# arduino2.net
KiCad netlist of a schematic drawn in EAGLE
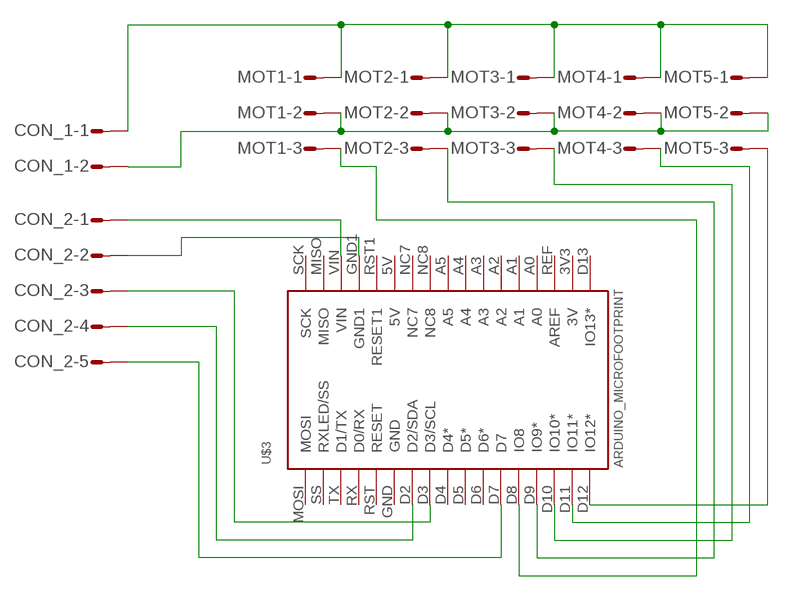
[diagram p0: schematic, sheet 1]

(export (version "E")
  (design (tool "Eeschema 10.0.6"))
  (components
    (comp (ref "CON_1")
      (value "S02P")
      (footprint "eagle-import:S02P")
      (libsource (lib "eagle-import") (part "S02P"))
    )
    (comp (ref "CON_2")
      (value "S05P")
      (footprint "eagle-import:S05P")
      (libsource (lib "eagle-import") (part "S05P"))
    )
    (comp (ref "MOT1")
      (value "S03P")
      (footprint "eagle-import:S03P")
      (libsource (lib "eagle-import") (part "S03P"))
    )
    (comp (ref "MOT2")
      (value "S03P")
      (footprint "eagle-import:S03P")
      (libsource (lib "eagle-import") (part "S03P"))
    )
    (comp (ref "MOT3")
      (value "S03P")
      (footprint "eagle-import:S03P")
      (libsource (lib "eagle-import") (part "S03P"))
    )
    (comp (ref "MOT4")
      (value "S03P")
      (footprint "eagle-import:S03P")
      (libsource (lib "eagle-import") (part "S03P"))
    )
    (comp (ref "MOT5")
      (value "S03P")
      (footprint "eagle-import:S03P")
      (libsource (lib "eagle-import") (part "S03P"))
    )
    (comp (ref "U$3")
      (value "ARDUINO_MICROFOOTPRINT")
      (footprint "eagle-import:ARDUINO-MICRO")
      (libsource (lib "eagle-import") (part "ARDUINO_MICROFOOTPRINT"))
    )
  )
  (nets
    (net (code "1") (name "Net-(CON_1A-S)") (class "Default")
      (node (ref "CON_1") (pin "1") (pinfunction "S_1") (pintype "passive"))
      (node (ref "MOT1") (pin "1") (pinfunction "S_1") (pintype "passive"))
      (node (ref "MOT2") (pin "1") (pinfunction "S_1") (pintype "passive"))
      (node (ref "MOT3") (pin "1") (pinfunction "S_1") (pintype "passive"))
      (node (ref "MOT4") (pin "1") (pinfunction "S_1") (pintype "passive"))
      (node (ref "MOT5") (pin "1") (pinfunction "S_1") (pintype "passive"))
    )
    (net (code "2") (name "Net-(CON_1B-S)") (class "Default")
      (node (ref "CON_1") (pin "2") (pinfunction "S_2") (pintype "passive"))
      (node (ref "MOT1") (pin "2") (pinfunction "S_2") (pintype "passive"))
      (node (ref "MOT2") (pin "2") (pinfunction "S_2") (pintype "passive"))
      (node (ref "MOT3") (pin "2") (pinfunction "S_2") (pintype "passive"))
      (node (ref "MOT4") (pin "2") (pinfunction "S_2") (pintype "passive"))
      (node (ref "MOT5") (pin "2") (pinfunction "S_2") (pintype "passive"))
    )
    (net (code "3") (name "Net-(CON_2A-S)") (class "Default")
      (node (ref "CON_2") (pin "1") (pinfunction "S_1") (pintype "passive"))
      (node (ref "U$3") (pin "VIN") (pinfunction "VIN_VIN") (pintype "bidirectional"))
    )
    (net (code "4") (name "Net-(CON_2B-S)") (class "Default")
      (node (ref "CON_2") (pin "2") (pinfunction "S_2") (pintype "passive"))
      (node (ref "U$3") (pin "GND1") (pinfunction "GND1_GND1") (pintype "bidirectional"))
    )
    (net (code "5") (name "Net-(CON_2C-S)") (class "Default")
      (node (ref "CON_2") (pin "3") (pinfunction "S_3") (pintype "passive"))
      (node (ref "U$3") (pin "D3") (pinfunction "D3/SCL_D3") (pintype "bidirectional"))
    )
    (net (code "6") (name "Net-(CON_2D-S)") (class "Default")
      (node (ref "CON_2") (pin "4") (pinfunction "S_4") (pintype "passive"))
      (node (ref "U$3") (pin "D2") (pinfunction "D2/SDA_D2") (pintype "bidirectional"))
    )
    (net (code "7") (name "Net-(CON_2E-S)") (class "Default")
      (node (ref "CON_2") (pin "5") (pinfunction "S_5") (pintype "passive"))
      (node (ref "U$3") (pin "D7") (pinfunction "D7_D7") (pintype "bidirectional"))
    )
    (net (code "8") (name "Net-(MOT1C-S)") (class "Default")
      (node (ref "MOT1") (pin "3") (pinfunction "S_3") (pintype "passive"))
      (node (ref "U$3") (pin "D8") (pinfunction "IO8_D8") (pintype "bidirectional"))
    )
    (net (code "9") (name "Net-(MOT2C-S)") (class "Default")
      (node (ref "MOT2") (pin "3") (pinfunction "S_3") (pintype "passive"))
      (node (ref "U$3") (pin "D9") (pinfunction "IO9*_D9") (pintype "bidirectional"))
    )
    (net (code "10") (name "Net-(MOT3C-S)") (class "Default")
      (node (ref "MOT3") (pin "3") (pinfunction "S_3") (pintype "passive"))
      (node (ref "U$3") (pin "D10") (pinfunction "IO10*_D10") (pintype "bidirectional"))
    )
    (net (code "11") (name "Net-(MOT4C-S)") (class "Default")
      (node (ref "MOT4") (pin "3") (pinfunction "S_3") (pintype "passive"))
      (node (ref "U$3") (pin "D11") (pinfunction "IO11*_D11") (pintype "bidirectional"))
    )
    (net (code "12") (name "Net-(MOT5C-S)") (class "Default")
      (node (ref "MOT5") (pin "3") (pinfunction "S_3") (pintype "passive"))
      (node (ref "U$3") (pin "D12") (pinfunction "IO12*_D12") (pintype "bidirectional"))
    )
    (net (code "13") (name "unconnected-(U$3-3V-Pad3V3)") (class "Default")
      (node (ref "U$3") (pin "3V3") (pinfunction "3V_3V3") (pintype "bidirectional"))
    )
    (net (code "14") (name "unconnected-(U$3-AREF-PadREF)") (class "Default")
      (node (ref "U$3") (pin "REF") (pinfunction "AREF_REF") (pintype "bidirectional"))
    )
    (net (code "15") (name "unconnected-(U$3-D0{slash}RX-PadRX)") (class "Default")
      (node (ref "U$3") (pin "RX") (pinfunction "D0/RX_RX") (pintype "bidirectional"))
    )
    (net (code "16") (name "unconnected-(U$3-D1{slash}TX-PadTX)") (class "Default")
      (node (ref "U$3") (pin "TX") (pinfunction "D1/TX_TX") (pintype "bidirectional"))
    )
    (net (code "17") (name "unconnected-(U$3-D4*-PadD4)") (class "Default")
      (node (ref "U$3") (pin "D4") (pinfunction "D4*_D4") (pintype "bidirectional"))
    )
    (net (code "18") (name "unconnected-(U$3-D5*-PadD5)") (class "Default")
      (node (ref "U$3") (pin "D5") (pinfunction "D5*_D5") (pintype "bidirectional"))
    )
    (net (code "19") (name "unconnected-(U$3-D6*-PadD6)") (class "Default")
      (node (ref "U$3") (pin "D6") (pinfunction "D6*_D6") (pintype "bidirectional"))
    )
    (net (code "20") (name "unconnected-(U$3-IO13*-PadD13)") (class "Default")
      (node (ref "U$3") (pin "D13") (pinfunction "IO13*_D13") (pintype "bidirectional"))
    )
    (net (code "21") (name "unconnected-(U$3-Pad5V)") (class "Default")
      (node (ref "U$3") (pin "5V") (pinfunction "5V_5V") (pintype "bidirectional"))
    )
    (net (code "22") (name "unconnected-(U$3-PadA0)") (class "Default")
      (node (ref "U$3") (pin "A0") (pinfunction "A0_A0") (pintype "bidirectional"))
    )
    (net (code "23") (name "unconnected-(U$3-PadA1)") (class "Default")
      (node (ref "U$3") (pin "A1") (pinfunction "A1_A1") (pintype "bidirectional"))
    )
    (net (code "24") (name "unconnected-(U$3-PadA2)") (class "Default")
      (node (ref "U$3") (pin "A2") (pinfunction "A2_A2") (pintype "bidirectional"))
    )
    (net (code "25") (name "unconnected-(U$3-PadA3)") (class "Default")
      (node (ref "U$3") (pin "A3") (pinfunction "A3_A3") (pintype "bidirectional"))
    )
    (net (code "26") (name "unconnected-(U$3-PadA4)") (class "Default")
      (node (ref "U$3") (pin "A4") (pinfunction "A4_A4") (pintype "bidirectional"))
    )
    (net (code "27") (name "unconnected-(U$3-PadA5)") (class "Default")
      (node (ref "U$3") (pin "A5") (pinfunction "A5_A5") (pintype "bidirectional"))
    )
    (net (code "28") (name "unconnected-(U$3-PadGND)") (class "Default")
      (node (ref "U$3") (pin "GND") (pinfunction "GND_GND") (pintype "bidirectional"))
    )
    (net (code "29") (name "unconnected-(U$3-PadMISO)") (class "Default")
      (node (ref "U$3") (pin "MISO") (pinfunction "MISO_MISO") (pintype "bidirectional"))
    )
    (net (code "30") (name "unconnected-(U$3-PadMOSI)") (class "Default")
      (node (ref "U$3") (pin "MOSI") (pinfunction "MOSI_MOSI") (pintype "bidirectional"))
    )
    (net (code "31") (name "unconnected-(U$3-PadNC7)") (class "Default")
      (node (ref "U$3") (pin "NC7") (pinfunction "NC7_NC7") (pintype "bidirectional"))
    )
    (net (code "32") (name "unconnected-(U$3-PadNC8)") (class "Default")
      (node (ref "U$3") (pin "NC8") (pinfunction "NC8_NC8") (pintype "bidirectional"))
    )
    (net (code "33") (name "unconnected-(U$3-PadSCK)") (class "Default")
      (node (ref "U$3") (pin "SCK") (pinfunction "SCK_SCK") (pintype "bidirectional"))
    )
    (net (code "34") (name "unconnected-(U$3-RESET-PadRST)") (class "Default")
      (node (ref "U$3") (pin "RST") (pinfunction "RESET_RST") (pintype "bidirectional"))
    )
    (net (code "35") (name "unconnected-(U$3-RESET1-PadRST1)") (class "Default")
      (node (ref "U$3") (pin "RST1") (pinfunction "RESET1_RST1") (pintype "bidirectional"))
    )
    (net (code "36") (name "unconnected-(U$3-RXLED{slash}SS-PadSS)") (class "Default")
      (node (ref "U$3") (pin "SS") (pinfunction "RXLED/SS_SS") (pintype "bidirectional"))
    )
  )
)
